# MCU.net
KiCad netlist of a schematic drawn in EAGLE
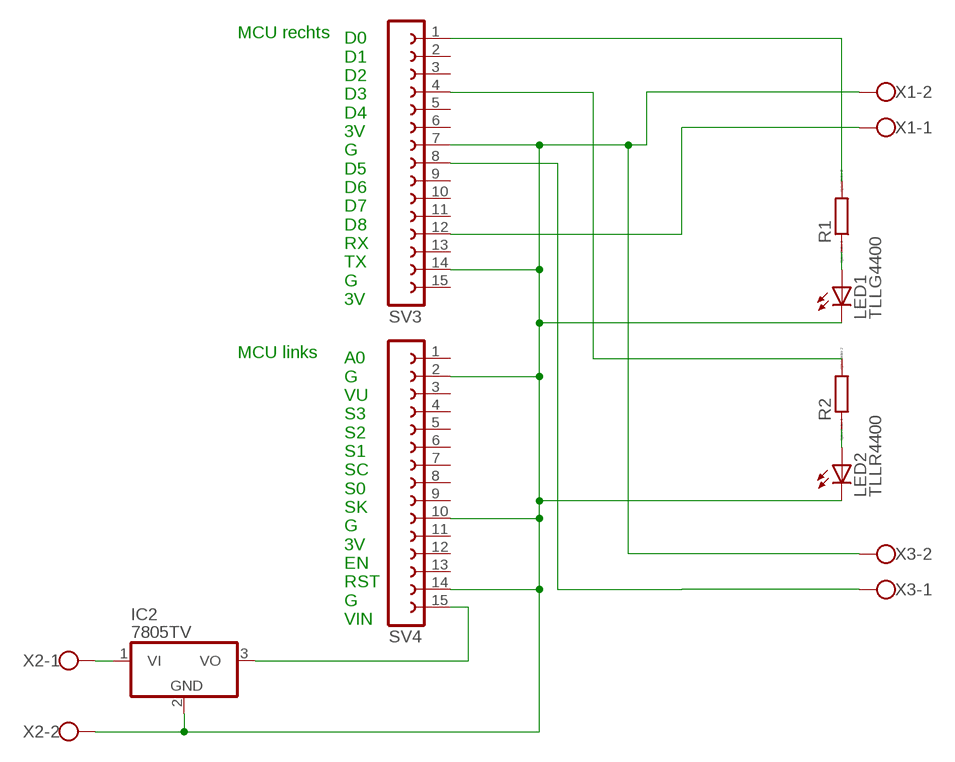
[diagram p0: schematic, sheet 1]

(export (version "E")
  (design (tool "Eeschema 10.0.6"))
  (components
    (comp (ref "IC2")
      (value "7805TV")
      (footprint "eagle-import:TO220V")
      (libsource (lib "eagle-import") (part "78TV05"))
    )
    (comp (ref "LED1")
      (value "TLLG4400")
      (footprint "eagle-import:LED3MM")
      (fields (field (name "MF") "VISHAY SEMICONDUCTOR"))
      (libsource (lib "eagle-import") (part "TLLG4400"))
    )
    (comp (ref "LED2")
      (value "TLLR4400")
      (footprint "eagle-import:LED3MM")
      (fields (field (name "MF") "VISHAY SEMICONDUCTOR"))
      (libsource (lib "eagle-import") (part "TLLR4400"))
    )
    (comp (ref "R1")
      (value "R0207/10")
      (footprint "eagle-import:0207_10")
      (libsource (lib "eagle-import") (part "R0207/10"))
    )
    (comp (ref "R2")
      (value "R0207/10")
      (footprint "eagle-import:0207_10")
      (libsource (lib "eagle-import") (part "R0207/10"))
    )
    (comp (ref "SV3")
      (value "FE15-1")
      (footprint "eagle-import:FE15")
      (libsource (lib "eagle-import") (part "FE15-1"))
    )
    (comp (ref "SV4")
      (value "FE15-1")
      (footprint "eagle-import:FE15")
      (libsource (lib "eagle-import") (part "FE15-1"))
    )
    (comp (ref "X1")
      (value "W237-102")
      (footprint "eagle-import:W237-102")
      (fields (field (name "MPN") "237-102"))
      (libsource (lib "eagle-import") (part "W237-102"))
    )
    (comp (ref "X2")
      (value "W237-102")
      (footprint "eagle-import:W237-102")
      (fields (field (name "MPN") "237-102"))
      (libsource (lib "eagle-import") (part "W237-102"))
    )
    (comp (ref "X3")
      (value "W237-102")
      (footprint "eagle-import:W237-102")
      (fields (field (name "MPN") "237-102"))
      (libsource (lib "eagle-import") (part "W237-102"))
    )
  )
  (nets
    (net (code "1") (name "Net-(IC2-GND)") (class "Default")
      (node (ref "IC2") (pin "2") (pinfunction "GND_2") (pintype "passive"))
      (node (ref "LED1") (pin "K") (pinfunction "C_K") (pintype "passive"))
      (node (ref "LED2") (pin "K") (pinfunction "C_K") (pintype "passive"))
      (node (ref "SV3") (pin "14") (pinfunction "14_14") (pintype "passive"))
      (node (ref "SV3") (pin "7") (pinfunction "7_7") (pintype "passive"))
      (node (ref "SV4") (pin "10") (pinfunction "10_10") (pintype "passive"))
      (node (ref "SV4") (pin "14") (pinfunction "14_14") (pintype "passive"))
      (node (ref "SV4") (pin "2") (pinfunction "2_2") (pintype "passive"))
      (node (ref "X1") (pin "2") (pinfunction "KL_2") (pintype "passive"))
      (node (ref "X2") (pin "2") (pinfunction "KL_2") (pintype "passive"))
      (node (ref "X3") (pin "2") (pinfunction "KL_2") (pintype "passive"))
    )
    (net (code "2") (name "Net-(IC2-VI)") (class "Default")
      (node (ref "IC2") (pin "1") (pinfunction "VI_1") (pintype "input"))
      (node (ref "X2") (pin "1") (pinfunction "KL_1") (pintype "passive"))
    )
    (net (code "3") (name "Net-(IC2-VO)") (class "Default")
      (node (ref "IC2") (pin "3") (pinfunction "VO_3") (pintype "passive"))
      (node (ref "SV4") (pin "15") (pinfunction "15_15") (pintype "passive"))
    )
    (net (code "4") (name "Net-(LED1-PadA)") (class "Default")
      (node (ref "LED1") (pin "A") (pinfunction "A_A") (pintype "passive"))
      (node (ref "R1") (pin "1") (pinfunction "1_1") (pintype "passive"))
    )
    (net (code "5") (name "Net-(LED2-PadA)") (class "Default")
      (node (ref "LED2") (pin "A") (pinfunction "A_A") (pintype "passive"))
      (node (ref "R2") (pin "1") (pinfunction "1_1") (pintype "passive"))
    )
    (net (code "6") (name "Net-(R1-Pad2)") (class "Default")
      (node (ref "R1") (pin "2") (pinfunction "2_2") (pintype "passive"))
      (node (ref "SV3") (pin "1") (pinfunction "1_1") (pintype "passive"))
    )
    (net (code "7") (name "Net-(R2-Pad2)") (class "Default")
      (node (ref "R2") (pin "2") (pinfunction "2_2") (pintype "passive"))
      (node (ref "SV3") (pin "4") (pinfunction "4_4") (pintype "passive"))
    )
    (net (code "8") (name "Net-(X1A-KL)") (class "Default")
      (node (ref "SV3") (pin "12") (pinfunction "12_12") (pintype "passive"))
      (node (ref "X1") (pin "1") (pinfunction "KL_1") (pintype "passive"))
    )
    (net (code "9") (name "Net-(X3A-KL)") (class "Default")
      (node (ref "SV3") (pin "8") (pinfunction "8_8") (pintype "passive"))
      (node (ref "X3") (pin "1") (pinfunction "KL_1") (pintype "passive"))
    )
    (net (code "10") (name "unconnected-(SV3-Pad2)") (class "Default")
      (node (ref "SV3") (pin "2") (pinfunction "2_2") (pintype "passive"))
    )
    (net (code "11") (name "unconnected-(SV3-Pad3)") (class "Default")
      (node (ref "SV3") (pin "3") (pinfunction "3_3") (pintype "passive"))
    )
    (net (code "12") (name "unconnected-(SV3-Pad5)") (class "Default")
      (node (ref "SV3") (pin "5") (pinfunction "5_5") (pintype "passive"))
    )
    (net (code "13") (name "unconnected-(SV3-Pad6)") (class "Default")
      (node (ref "SV3") (pin "6") (pinfunction "6_6") (pintype "passive"))
    )
    (net (code "14") (name "unconnected-(SV3-Pad9)") (class "Default")
      (node (ref "SV3") (pin "9") (pinfunction "9_9") (pintype "passive"))
    )
    (net (code "15") (name "unconnected-(SV3-Pad10)") (class "Default")
      (node (ref "SV3") (pin "10") (pinfunction "10_10") (pintype "passive"))
    )
    (net (code "16") (name "unconnected-(SV3-Pad11)") (class "Default")
      (node (ref "SV3") (pin "11") (pinfunction "11_11") (pintype "passive"))
    )
    (net (code "17") (name "unconnected-(SV3-Pad13)") (class "Default")
      (node (ref "SV3") (pin "13") (pinfunction "13_13") (pintype "passive"))
    )
    (net (code "18") (name "unconnected-(SV3-Pad15)") (class "Default")
      (node (ref "SV3") (pin "15") (pinfunction "15_15") (pintype "passive"))
    )
    (net (code "19") (name "unconnected-(SV4-Pad1)") (class "Default")
      (node (ref "SV4") (pin "1") (pinfunction "1_1") (pintype "passive"))
    )
    (net (code "20") (name "unconnected-(SV4-Pad3)") (class "Default")
      (node (ref "SV4") (pin "3") (pinfunction "3_3") (pintype "passive"))
    )
    (net (code "21") (name "unconnected-(SV4-Pad4)") (class "Default")
      (node (ref "SV4") (pin "4") (pinfunction "4_4") (pintype "passive"))
    )
    (net (code "22") (name "unconnected-(SV4-Pad5)") (class "Default")
      (node (ref "SV4") (pin "5") (pinfunction "5_5") (pintype "passive"))
    )
    (net (code "23") (name "unconnected-(SV4-Pad6)") (class "Default")
      (node (ref "SV4") (pin "6") (pinfunction "6_6") (pintype "passive"))
    )
    (net (code "24") (name "unconnected-(SV4-Pad7)") (class "Default")
      (node (ref "SV4") (pin "7") (pinfunction "7_7") (pintype "passive"))
    )
    (net (code "25") (name "unconnected-(SV4-Pad8)") (class "Default")
      (node (ref "SV4") (pin "8") (pinfunction "8_8") (pintype "passive"))
    )
    (net (code "26") (name "unconnected-(SV4-Pad9)") (class "Default")
      (node (ref "SV4") (pin "9") (pinfunction "9_9") (pintype "passive"))
    )
    (net (code "27") (name "unconnected-(SV4-Pad11)") (class "Default")
      (node (ref "SV4") (pin "11") (pinfunction "11_11") (pintype "passive"))
    )
    (net (code "28") (name "unconnected-(SV4-Pad12)") (class "Default")
      (node (ref "SV4") (pin "12") (pinfunction "12_12") (pintype "passive"))
    )
    (net (code "29") (name "unconnected-(SV4-Pad13)") (class "Default")
      (node (ref "SV4") (pin "13") (pinfunction "13_13") (pintype "passive"))
    )
  )
)
